# ZasilanieLED.net
KiCad netlist of a schematic drawn in EAGLE
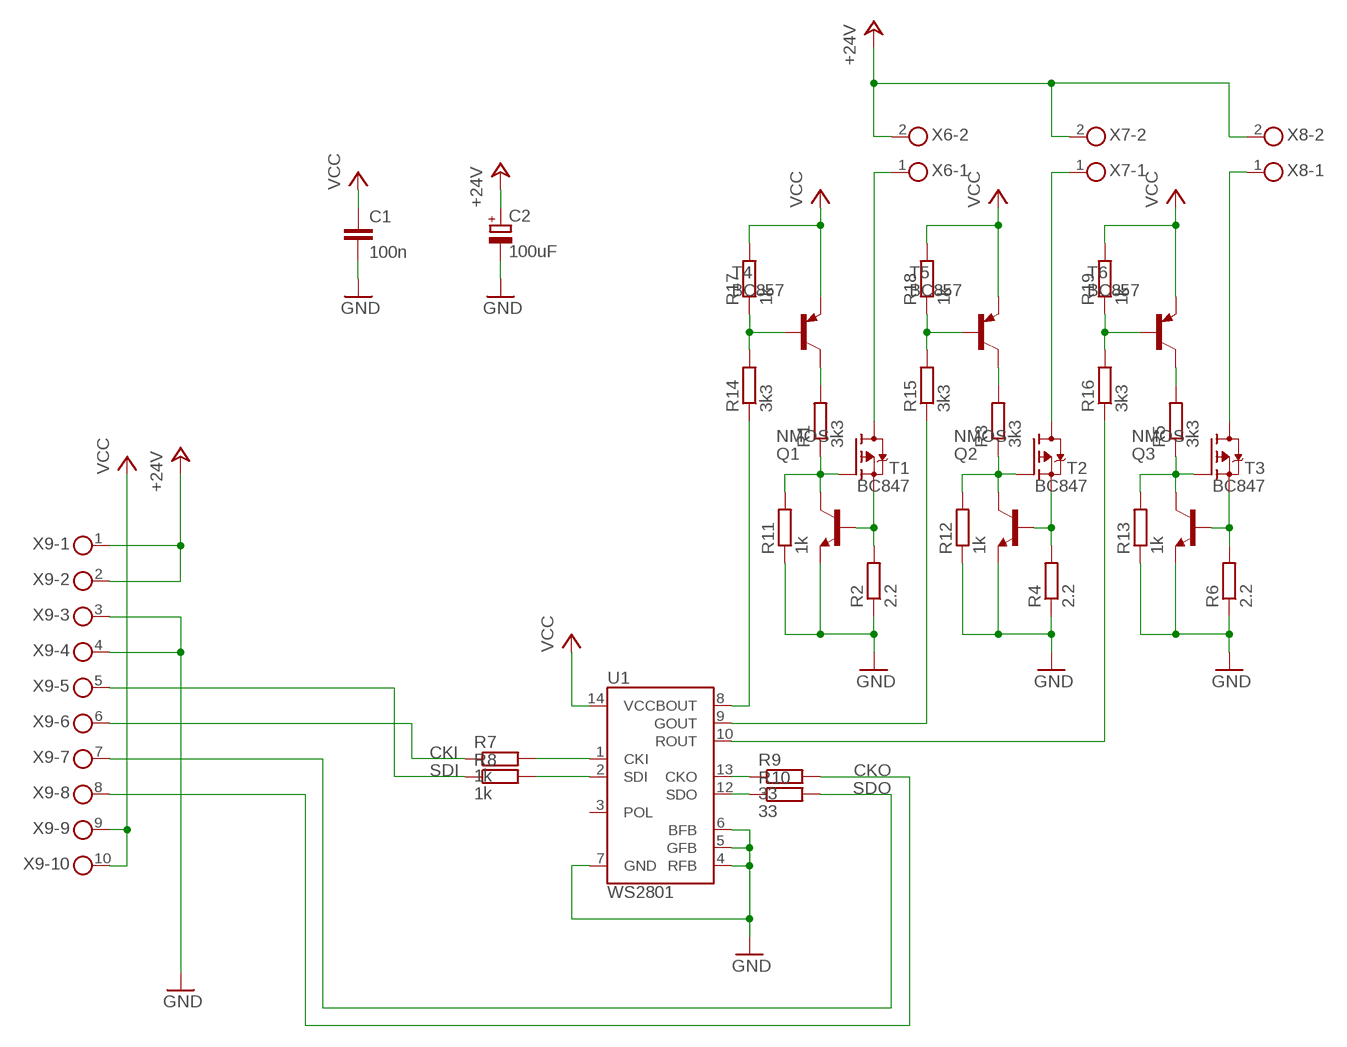
[diagram p0: schematic, sheet 1]

(export (version "E")
  (design (tool "Eeschema 10.0.6"))
  (components
    (comp (ref "C1")
      (value "100n")
      (footprint "eagle-import:C1206")
      (libsource (lib "eagle-import") (part "C-EUC1206"))
    )
    (comp (ref "C2")
      (value "100uF")
      (footprint "eagle-import:E5-10,5")
      (libsource (lib "eagle-import") (part "CPOL-EUE5-10.5"))
    )
    (comp (ref "Q1")
      (value "NMOS")
      (footprint "eagle-import:TO252")
      (libsource (lib "eagle-import") (part "SPD30P06PTO252"))
    )
    (comp (ref "Q2")
      (value "NMOS")
      (footprint "eagle-import:TO252")
      (libsource (lib "eagle-import") (part "SPD30P06PTO252"))
    )
    (comp (ref "Q3")
      (value "NMOS")
      (footprint "eagle-import:TO252")
      (libsource (lib "eagle-import") (part "SPD30P06PTO252"))
    )
    (comp (ref "R1")
      (value "3k3")
      (footprint "eagle-import:R1206")
      (libsource (lib "eagle-import") (part "R-EU_R1206"))
    )
    (comp (ref "R2")
      (value "2.2")
      (footprint "eagle-import:0207_10")
      (libsource (lib "eagle-import") (part "R-EU_0207/10"))
    )
    (comp (ref "R3")
      (value "3k3")
      (footprint "eagle-import:R1206")
      (libsource (lib "eagle-import") (part "R-EU_R1206"))
    )
    (comp (ref "R4")
      (value "2.2")
      (footprint "eagle-import:0207_10")
      (libsource (lib "eagle-import") (part "R-EU_0207/10"))
    )
    (comp (ref "R5")
      (value "3k3")
      (footprint "eagle-import:R1206")
      (libsource (lib "eagle-import") (part "R-EU_R1206"))
    )
    (comp (ref "R6")
      (value "2.2")
      (footprint "eagle-import:0207_10")
      (libsource (lib "eagle-import") (part "R-EU_0207/10"))
    )
    (comp (ref "R7")
      (value "1k")
      (footprint "eagle-import:R1206")
      (libsource (lib "eagle-import") (part "R-EU_R1206"))
    )
    (comp (ref "R8")
      (value "1k")
      (footprint "eagle-import:R1206")
      (libsource (lib "eagle-import") (part "R-EU_R1206"))
    )
    (comp (ref "R9")
      (value "33")
      (footprint "eagle-import:R1206")
      (libsource (lib "eagle-import") (part "R-EU_R1206"))
    )
    (comp (ref "R10")
      (value "33")
      (footprint "eagle-import:R1206")
      (libsource (lib "eagle-import") (part "R-EU_R1206"))
    )
    (comp (ref "R11")
      (value "1k")
      (footprint "eagle-import:R1206")
      (libsource (lib "eagle-import") (part "R-EU_R1206"))
    )
    (comp (ref "R12")
      (value "1k")
      (footprint "eagle-import:R1206")
      (libsource (lib "eagle-import") (part "R-EU_R1206"))
    )
    (comp (ref "R13")
      (value "1k")
      (footprint "eagle-import:R1206")
      (libsource (lib "eagle-import") (part "R-EU_R1206"))
    )
    (comp (ref "R14")
      (value "3k3")
      (footprint "eagle-import:R1206")
      (libsource (lib "eagle-import") (part "R-EU_R1206"))
    )
    (comp (ref "R15")
      (value "3k3")
      (footprint "eagle-import:R1206")
      (libsource (lib "eagle-import") (part "R-EU_R1206"))
    )
    (comp (ref "R16")
      (value "3k3")
      (footprint "eagle-import:R1206")
      (libsource (lib "eagle-import") (part "R-EU_R1206"))
    )
    (comp (ref "R17")
      (value "1k")
      (footprint "eagle-import:R1206")
      (libsource (lib "eagle-import") (part "R-EU_R1206"))
    )
    (comp (ref "R18")
      (value "1k")
      (footprint "eagle-import:R1206")
      (libsource (lib "eagle-import") (part "R-EU_R1206"))
    )
    (comp (ref "R19")
      (value "1k")
      (footprint "eagle-import:R1206")
      (libsource (lib "eagle-import") (part "R-EU_R1206"))
    )
    (comp (ref "T1")
      (value "BC847")
      (footprint "eagle-import:SOT23")
      (libsource (lib "eagle-import") (part "BC847"))
    )
    (comp (ref "T2")
      (value "BC847")
      (footprint "eagle-import:SOT23")
      (libsource (lib "eagle-import") (part "BC847"))
    )
    (comp (ref "T3")
      (value "BC847")
      (footprint "eagle-import:SOT23")
      (libsource (lib "eagle-import") (part "BC847"))
    )
    (comp (ref "T4")
      (value "BC857")
      (footprint "eagle-import:SOT23-BEC")
      (libsource (lib "eagle-import") (part "-PNP-SOT23-BECBC857A"))
    )
    (comp (ref "T5")
      (value "BC857")
      (footprint "eagle-import:SOT23-BEC")
      (libsource (lib "eagle-import") (part "-PNP-SOT23-BECBC857A"))
    )
    (comp (ref "T6")
      (value "BC857")
      (footprint "eagle-import:SOT23-BEC")
      (libsource (lib "eagle-import") (part "-PNP-SOT23-BECBC857A"))
    )
    (comp (ref "U1")
      (value "WS2801")
      (footprint "eagle-import:SOP-14")
      (libsource (lib "eagle-import") (part "WS2801"))
    )
    (comp (ref "X6")
      (value "AKL59-02")
      (footprint "eagle-import:2POL35")
      (libsource (lib "eagle-import") (part "AKL59-02"))
    )
    (comp (ref "X7")
      (value "AKL59-02")
      (footprint "eagle-import:2POL35")
      (libsource (lib "eagle-import") (part "AKL59-02"))
    )
    (comp (ref "X8")
      (value "AKL59-02")
      (footprint "eagle-import:2POL35")
      (libsource (lib "eagle-import") (part "AKL59-02"))
    )
    (comp (ref "X9")
      (value "AKL59-10")
      (footprint "eagle-import:10POL35")
      (libsource (lib "eagle-import") (part "AKL59-10"))
    )
  )
  (nets
    (net (code "1") (name "+24V") (class "Default")
      (node (ref "C2") (pin "+") (pinfunction "+_+") (pintype "passive"))
      (node (ref "X6") (pin "2") (pinfunction "1_2") (pintype "passive"))
      (node (ref "X7") (pin "2") (pinfunction "1_2") (pintype "passive"))
      (node (ref "X8") (pin "2") (pinfunction "1_2") (pintype "passive"))
      (node (ref "X9") (pin "1") (pinfunction "1_1") (pintype "passive"))
      (node (ref "X9") (pin "2") (pinfunction "1_2") (pintype "passive"))
    )
    (net (code "2") (name "/CKI") (class "Default")
      (node (ref "R7") (pin "1") (pinfunction "1_1") (pintype "passive"))
      (node (ref "X9") (pin "6") (pinfunction "1_6") (pintype "passive"))
    )
    (net (code "3") (name "/CKO") (class "Default")
      (node (ref "R9") (pin "2") (pinfunction "2_2") (pintype "passive"))
      (node (ref "X9") (pin "8") (pinfunction "1_8") (pintype "passive"))
    )
    (net (code "4") (name "/SDI") (class "Default")
      (node (ref "R8") (pin "1") (pinfunction "1_1") (pintype "passive"))
      (node (ref "X9") (pin "5") (pinfunction "1_5") (pintype "passive"))
    )
    (net (code "5") (name "/SDO") (class "Default")
      (node (ref "R10") (pin "2") (pinfunction "2_2") (pintype "passive"))
      (node (ref "X9") (pin "7") (pinfunction "1_7") (pintype "passive"))
    )
    (net (code "6") (name "GND") (class "Default")
      (node (ref "C1") (pin "2") (pinfunction "2_2") (pintype "passive"))
      (node (ref "C2") (pin "-") (pinfunction "-_-") (pintype "passive"))
      (node (ref "R11") (pin "1") (pinfunction "1_1") (pintype "passive"))
      (node (ref "R12") (pin "1") (pinfunction "1_1") (pintype "passive"))
      (node (ref "R13") (pin "1") (pinfunction "1_1") (pintype "passive"))
      (node (ref "R2") (pin "1") (pinfunction "1_1") (pintype "passive"))
      (node (ref "R4") (pin "1") (pinfunction "1_1") (pintype "passive"))
      (node (ref "R6") (pin "1") (pinfunction "1_1") (pintype "passive"))
      (node (ref "T1") (pin "2") (pinfunction "E_2") (pintype "passive"))
      (node (ref "T2") (pin "2") (pinfunction "E_2") (pintype "passive"))
      (node (ref "T3") (pin "2") (pinfunction "E_2") (pintype "passive"))
      (node (ref "U1") (pin "4") (pinfunction "RFB_4") (pintype "bidirectional"))
      (node (ref "U1") (pin "5") (pinfunction "GFB_5") (pintype "bidirectional"))
      (node (ref "U1") (pin "6") (pinfunction "BFB_6") (pintype "bidirectional"))
      (node (ref "U1") (pin "7") (pinfunction "GND_7") (pintype "bidirectional"))
      (node (ref "X9") (pin "3") (pinfunction "1_3") (pintype "passive"))
      (node (ref "X9") (pin "4") (pinfunction "1_4") (pintype "passive"))
    )
    (net (code "7") (name "Net-(Q1-D)") (class "Default")
      (node (ref "Q1") (pin "3") (pinfunction "D_3") (pintype "passive"))
      (node (ref "X6") (pin "1") (pinfunction "1_1") (pintype "passive"))
    )
    (net (code "8") (name "Net-(Q1-G)") (class "Default")
      (node (ref "Q1") (pin "1") (pinfunction "G_1") (pintype "passive"))
      (node (ref "R1") (pin "1") (pinfunction "1_1") (pintype "passive"))
      (node (ref "R11") (pin "2") (pinfunction "2_2") (pintype "passive"))
      (node (ref "T1") (pin "3") (pinfunction "C_3") (pintype "passive"))
    )
    (net (code "9") (name "Net-(Q1-S)") (class "Default")
      (node (ref "Q1") (pin "2") (pinfunction "S_2") (pintype "passive"))
      (node (ref "R2") (pin "2") (pinfunction "2_2") (pintype "passive"))
      (node (ref "T1") (pin "1") (pinfunction "B_1") (pintype "passive"))
    )
    (net (code "10") (name "Net-(Q2-D)") (class "Default")
      (node (ref "Q2") (pin "3") (pinfunction "D_3") (pintype "passive"))
      (node (ref "X7") (pin "1") (pinfunction "1_1") (pintype "passive"))
    )
    (net (code "11") (name "Net-(Q2-G)") (class "Default")
      (node (ref "Q2") (pin "1") (pinfunction "G_1") (pintype "passive"))
      (node (ref "R12") (pin "2") (pinfunction "2_2") (pintype "passive"))
      (node (ref "R3") (pin "1") (pinfunction "1_1") (pintype "passive"))
      (node (ref "T2") (pin "3") (pinfunction "C_3") (pintype "passive"))
    )
    (net (code "12") (name "Net-(Q2-S)") (class "Default")
      (node (ref "Q2") (pin "2") (pinfunction "S_2") (pintype "passive"))
      (node (ref "R4") (pin "2") (pinfunction "2_2") (pintype "passive"))
      (node (ref "T2") (pin "1") (pinfunction "B_1") (pintype "passive"))
    )
    (net (code "13") (name "Net-(Q3-D)") (class "Default")
      (node (ref "Q3") (pin "3") (pinfunction "D_3") (pintype "passive"))
      (node (ref "X8") (pin "1") (pinfunction "1_1") (pintype "passive"))
    )
    (net (code "14") (name "Net-(Q3-G)") (class "Default")
      (node (ref "Q3") (pin "1") (pinfunction "G_1") (pintype "passive"))
      (node (ref "R13") (pin "2") (pinfunction "2_2") (pintype "passive"))
      (node (ref "R5") (pin "1") (pinfunction "1_1") (pintype "passive"))
      (node (ref "T3") (pin "3") (pinfunction "C_3") (pintype "passive"))
    )
    (net (code "15") (name "Net-(Q3-S)") (class "Default")
      (node (ref "Q3") (pin "2") (pinfunction "S_2") (pintype "passive"))
      (node (ref "R6") (pin "2") (pinfunction "2_2") (pintype "passive"))
      (node (ref "T3") (pin "1") (pinfunction "B_1") (pintype "passive"))
    )
    (net (code "16") (name "Net-(R1-Pad2)") (class "Default")
      (node (ref "R1") (pin "2") (pinfunction "2_2") (pintype "passive"))
      (node (ref "T4") (pin "C") (pinfunction "C_C") (pintype "passive"))
    )
    (net (code "17") (name "Net-(R3-Pad2)") (class "Default")
      (node (ref "R3") (pin "2") (pinfunction "2_2") (pintype "passive"))
      (node (ref "T5") (pin "C") (pinfunction "C_C") (pintype "passive"))
    )
    (net (code "18") (name "Net-(R5-Pad2)") (class "Default")
      (node (ref "R5") (pin "2") (pinfunction "2_2") (pintype "passive"))
      (node (ref "T6") (pin "C") (pinfunction "C_C") (pintype "passive"))
    )
    (net (code "19") (name "Net-(R14-Pad2)") (class "Default")
      (node (ref "R14") (pin "2") (pinfunction "2_2") (pintype "passive"))
      (node (ref "R17") (pin "1") (pinfunction "1_1") (pintype "passive"))
      (node (ref "T4") (pin "B") (pinfunction "B_B") (pintype "passive"))
    )
    (net (code "20") (name "Net-(R15-Pad2)") (class "Default")
      (node (ref "R15") (pin "2") (pinfunction "2_2") (pintype "passive"))
      (node (ref "R18") (pin "1") (pinfunction "1_1") (pintype "passive"))
      (node (ref "T5") (pin "B") (pinfunction "B_B") (pintype "passive"))
    )
    (net (code "21") (name "Net-(R16-Pad2)") (class "Default")
      (node (ref "R16") (pin "2") (pinfunction "2_2") (pintype "passive"))
      (node (ref "R19") (pin "1") (pinfunction "1_1") (pintype "passive"))
      (node (ref "T6") (pin "B") (pinfunction "B_B") (pintype "passive"))
    )
    (net (code "22") (name "Net-(U1-BOUT)") (class "Default")
      (node (ref "R14") (pin "1") (pinfunction "1_1") (pintype "passive"))
      (node (ref "U1") (pin "8") (pinfunction "BOUT_8") (pintype "bidirectional"))
    )
    (net (code "23") (name "Net-(U1-CKI)") (class "Default")
      (node (ref "R7") (pin "2") (pinfunction "2_2") (pintype "passive"))
      (node (ref "U1") (pin "1") (pinfunction "CKI_1") (pintype "bidirectional"))
    )
    (net (code "24") (name "Net-(U1-CKO)") (class "Default")
      (node (ref "R9") (pin "1") (pinfunction "1_1") (pintype "passive"))
      (node (ref "U1") (pin "13") (pinfunction "CKO_13") (pintype "bidirectional"))
    )
    (net (code "25") (name "Net-(U1-GOUT)") (class "Default")
      (node (ref "R15") (pin "1") (pinfunction "1_1") (pintype "passive"))
      (node (ref "U1") (pin "9") (pinfunction "GOUT_9") (pintype "bidirectional"))
    )
    (net (code "26") (name "Net-(U1-ROUT)") (class "Default")
      (node (ref "R16") (pin "1") (pinfunction "1_1") (pintype "passive"))
      (node (ref "U1") (pin "10") (pinfunction "ROUT_10") (pintype "bidirectional"))
    )
    (net (code "27") (name "Net-(U1-SDI)") (class "Default")
      (node (ref "R8") (pin "2") (pinfunction "2_2") (pintype "passive"))
      (node (ref "U1") (pin "2") (pinfunction "SDI_2") (pintype "bidirectional"))
    )
    (net (code "28") (name "Net-(U1-SDO)") (class "Default")
      (node (ref "R10") (pin "1") (pinfunction "1_1") (pintype "passive"))
      (node (ref "U1") (pin "12") (pinfunction "SDO_12") (pintype "bidirectional"))
    )
    (net (code "29") (name "VCC") (class "Default")
      (node (ref "C1") (pin "1") (pinfunction "1_1") (pintype "passive"))
      (node (ref "R17") (pin "2") (pinfunction "2_2") (pintype "passive"))
      (node (ref "R18") (pin "2") (pinfunction "2_2") (pintype "passive"))
      (node (ref "R19") (pin "2") (pinfunction "2_2") (pintype "passive"))
      (node (ref "T4") (pin "E") (pinfunction "E_E") (pintype "passive"))
      (node (ref "T5") (pin "E") (pinfunction "E_E") (pintype "passive"))
      (node (ref "T6") (pin "E") (pinfunction "E_E") (pintype "passive"))
      (node (ref "U1") (pin "14") (pinfunction "VCC_14") (pintype "bidirectional"))
      (node (ref "X9") (pin "10") (pinfunction "1_10") (pintype "passive"))
      (node (ref "X9") (pin "9") (pinfunction "1_9") (pintype "passive"))
    )
    (net (code "30") (name "unconnected-(U1-POL-Pad3)") (class "Default")
      (node (ref "U1") (pin "3") (pinfunction "POL_3") (pintype "bidirectional"))
    )
  )
)
